# STM32F103C8T6_MinimumCoreBoard.net
KiCad netlist of a schematic drawn in Altium Designer
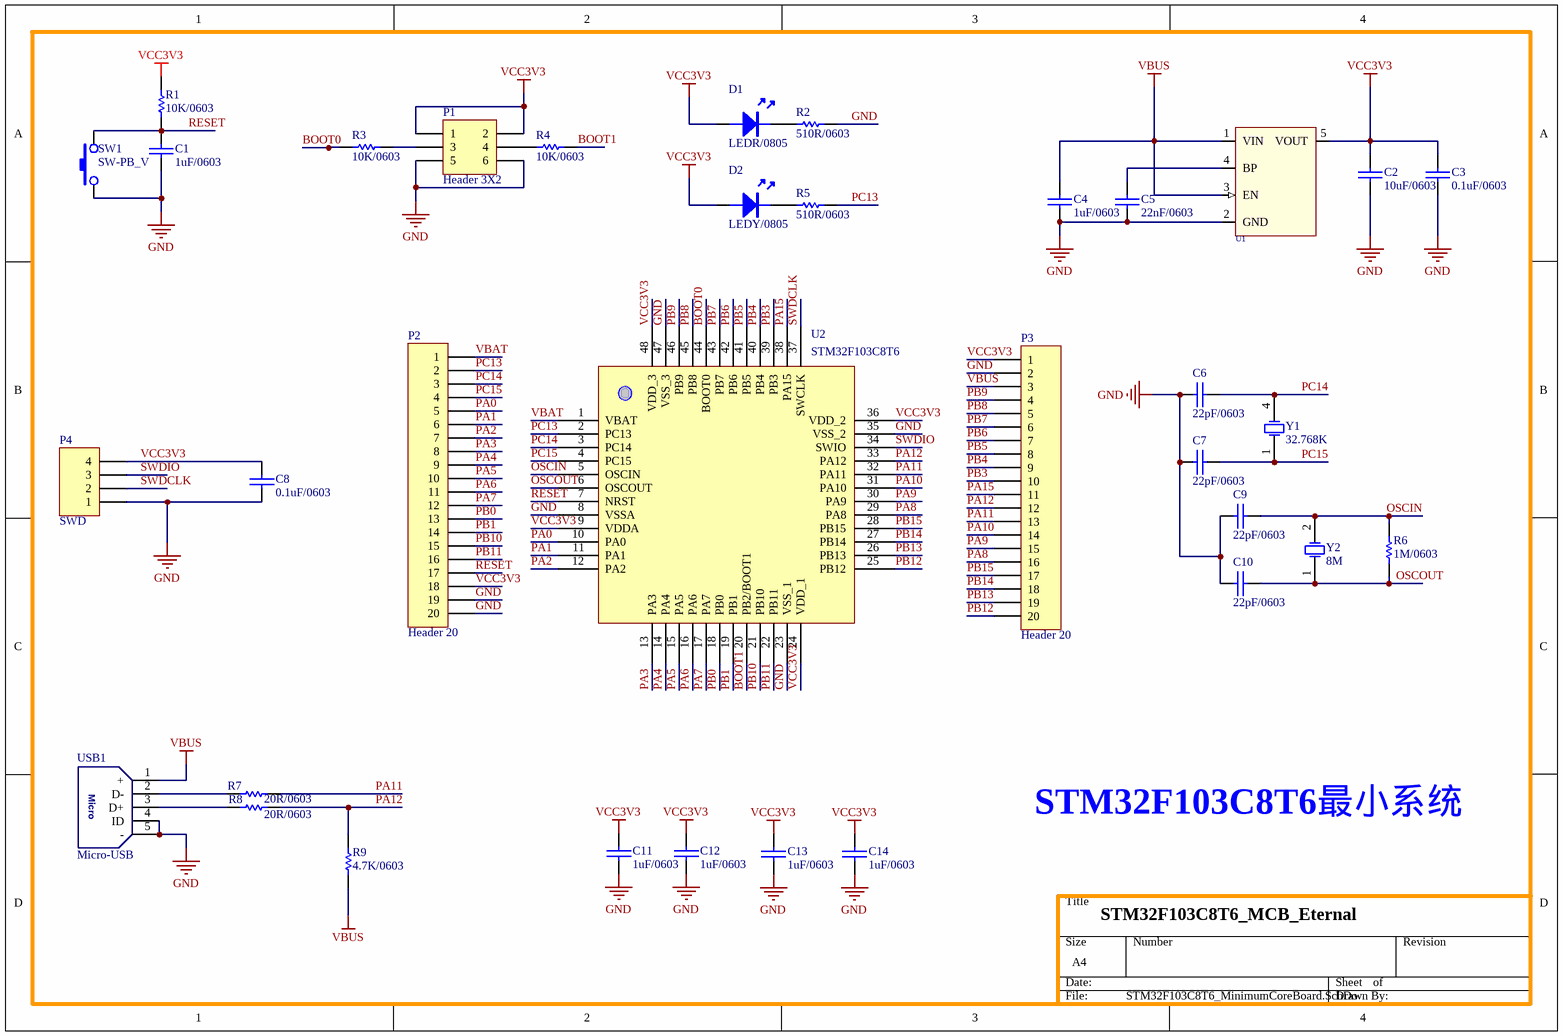
[diagram p0: STM32F103C8T6_MinimumCoreBoard.SchDoc]

(export (version "E")
  (design (tool "Eeschema 10.0.6"))
  (components
    (comp (ref "C1")
      (value "1uF/0603")
      (footprint "0603C")
      (description "无极性电容")
      (libsource (lib "电容") (part "CAP"))
    )
    (comp (ref "C2")
      (value "10uF/0603")
      (footprint "0603C")
      (description "无极性电容")
      (libsource (lib "电容") (part "CAP"))
    )
    (comp (ref "C3")
      (value "0.1uF/0603")
      (footprint "0603C")
      (description "无极性电容")
      (libsource (lib "电容") (part "CAP"))
    )
    (comp (ref "C4")
      (value "1uF/0603")
      (footprint "0603C")
      (description "无极性电容")
      (libsource (lib "电容") (part "CAP"))
    )
    (comp (ref "C5")
      (value "22nF/0603")
      (footprint "0603C")
      (description "无极性电容")
      (libsource (lib "电容") (part "CAP"))
    )
    (comp (ref "C6")
      (value "22pF/0603")
      (footprint "0603C")
      (description "无极性电容")
      (libsource (lib "电容") (part "CAP"))
    )
    (comp (ref "C7")
      (value "22pF/0603")
      (footprint "0603C")
      (description "无极性电容")
      (libsource (lib "电容") (part "CAP"))
    )
    (comp (ref "C8")
      (value "0.1uF/0603")
      (footprint "0603C")
      (description "无极性电容")
      (libsource (lib "电容") (part "CAP"))
    )
    (comp (ref "C9")
      (value "22pF/0603")
      (footprint "0603C")
      (description "无极性电容")
      (libsource (lib "电容") (part "CAP"))
    )
    (comp (ref "C10")
      (value "22pF/0603")
      (footprint "0603C")
      (description "无极性电容")
      (libsource (lib "电容") (part "CAP"))
    )
    (comp (ref "C11")
      (value "1uF/0603")
      (footprint "0603C")
      (description "无极性电容")
      (libsource (lib "电容") (part "CAP"))
    )
    (comp (ref "C12")
      (value "1uF/0603")
      (footprint "0603C")
      (description "无极性电容")
      (libsource (lib "电容") (part "CAP"))
    )
    (comp (ref "C13")
      (value "1uF/0603")
      (footprint "0603C")
      (description "无极性电容")
      (libsource (lib "电容") (part "CAP"))
    )
    (comp (ref "C14")
      (value "1uF/0603")
      (footprint "0603C")
      (description "无极性电容")
      (libsource (lib "电容") (part "CAP"))
    )
    (comp (ref "D1") (value "LEDR/0805") (footprint "LED-0805R") (libsource (lib "LED") (part "LED")))
    (comp (ref "D2") (value "LEDY/0805") (footprint "LED-0805Y") (libsource (lib "LED") (part "LED")))
    (comp (ref "P1")
      (value "Header 3X2")
      (footprint "HDR-3X2")
      (description "Header, 3-Pin, Dual row")
      (fields (field (name "PUBLISHER") "Altium Limited"))
      (libsource (lib "STM32F103C8T6") (part "Header 3X2"))
    )
    (comp (ref "P2")
      (value "Header 20")
      (footprint "HDR1X20")
      (description "Header, 20-Pin")
      (fields (field (name "PUBLISHER") "Altium Limited"))
      (libsource (lib "STM32F103C8T6") (part "Header 20"))
    )
    (comp (ref "P3")
      (value "Header 20")
      (footprint "HDR1X20")
      (description "Header, 20-Pin")
      (fields (field (name "PUBLISHER") "Altium Limited"))
      (libsource (lib "") (part "Header 20_1"))
    )
    (comp (ref "P4")
      (value "SWD")
      (footprint "HDR-1X4_H")
      (description "Header, 4-Pin")
      (fields (field (name "PUBLISHER") "Altium Limited"))
      (libsource (lib "STM32F103C8T6") (part "Header 4"))
    )
    (comp (ref "R1") (value "10K/0603") (footprint "0603R") (libsource (lib "电阻") (part "RES")))
    (comp (ref "R2") (value "510R/0603") (footprint "0603R") (libsource (lib "电阻") (part "RES")))
    (comp (ref "R3") (value "10K/0603") (footprint "0603R") (libsource (lib "电阻") (part "RES")))
    (comp (ref "R4") (value "10K/0603") (footprint "0603R") (libsource (lib "电阻") (part "RES")))
    (comp (ref "R5") (value "510R/0603") (footprint "0603R") (libsource (lib "电阻") (part "RES")))
    (comp (ref "R6") (value "1M/0603") (footprint "0603R") (libsource (lib "电阻") (part "RES")))
    (comp (ref "R7") (value "20R/0603") (footprint "0603R") (libsource (lib "电阻") (part "RES")))
    (comp (ref "R8") (value "20R/0603") (footprint "0603R") (libsource (lib "电阻") (part "RES")))
    (comp (ref "R9") (value "4.7K/0603") (footprint "0603R") (libsource (lib "电阻") (part "RES")))
    (comp (ref "SW1")
      (value "SW-PB_V")
      (footprint "TSW SMD-3*6*2.5")
      (description "SWITCH")
      (libsource (lib "STM32F103C8T6") (part "SW-PB_V"))
    )
    (comp (ref "U1")
      (value "RT9193")
      (footprint "SOT23-5L")
      (fields (field (name "ICA_PARTNUM") "$$2191094$$RT9193-15CU5") (field (name "PART NUMBER") "TMP-13"))
      (libsource (lib "STM32F103C8T6") (part "RT9193X_5P"))
    )
    (comp (ref "U2")
      (value "STM32F103C8T6")
      (footprint "TQFP48 7x7_L")
      (libsource (lib "STM32F103C8T6") (part "STM32F103C8T6"))
    )
    (comp (ref "USB1")
      (value "Micro-USB")
      (footprint "USB-micro_B")
      (libsource (lib "USB") (part "Micro-USB"))
    )
    (comp (ref "Y1")
      (value "32.768K")
      (footprint "MC-306")
      (description "Crystal Oscillator")
      (fields (field (name "PUBLISHER") "Altium Limited"))
      (libsource (lib "") (part "XTAL_1"))
    )
    (comp (ref "Y2")
      (value "8M")
      (footprint "XTAL-49S DIP")
      (description "Crystal Oscillator")
      (fields (field (name "PUBLISHER") "Altium Limited"))
      (libsource (lib "STM32F103C8T6") (part "XTAL"))
    )
  )
  (nets
    (net (code "1") (name "/BOOT0") (class "Default")
      (node (ref "R3") (pin "1") (pinfunction "1_1") (pintype "passive"))
      (node (ref "U2") (pin "44") (pinfunction "BOOT0_44") (pintype "passive"))
    )
    (net (code "2") (name "/BOOT1") (class "Default")
      (node (ref "R4") (pin "2") (pinfunction "2_2") (pintype "passive"))
      (node (ref "U2") (pin "20") (pinfunction "PB2/BOOT1_20") (pintype "passive"))
    )
    (net (code "3") (name "/OSCIN") (class "Default")
      (node (ref "C9") (pin "1") (pinfunction "1_1") (pintype "passive"))
      (node (ref "R6") (pin "2") (pinfunction "2_2") (pintype "passive"))
      (node (ref "U2") (pin "5") (pinfunction "OSCIN_5") (pintype "passive"))
      (node (ref "Y2") (pin "2") (pinfunction "OSC2_2") (pintype "passive"))
    )
    (net (code "4") (name "/OSCOUT") (class "Default")
      (node (ref "C10") (pin "1") (pinfunction "1_1") (pintype "passive"))
      (node (ref "R6") (pin "1") (pinfunction "1_1") (pintype "passive"))
      (node (ref "U2") (pin "6") (pinfunction "OSCOUT_6") (pintype "passive"))
      (node (ref "Y2") (pin "1") (pinfunction "OSC1_1") (pintype "passive"))
    )
    (net (code "5") (name "/PA0") (class "Default")
      (node (ref "P2") (pin "5") (pinfunction "5_5") (pintype "passive"))
      (node (ref "U2") (pin "10") (pinfunction "PA0_10") (pintype "passive"))
    )
    (net (code "6") (name "/PA1") (class "Default")
      (node (ref "P2") (pin "6") (pinfunction "6_6") (pintype "passive"))
      (node (ref "U2") (pin "11") (pinfunction "PA1_11") (pintype "passive"))
    )
    (net (code "7") (name "/PA2") (class "Default")
      (node (ref "P2") (pin "7") (pinfunction "7_7") (pintype "passive"))
      (node (ref "U2") (pin "12") (pinfunction "PA2_12") (pintype "passive"))
    )
    (net (code "8") (name "/PA3") (class "Default")
      (node (ref "P2") (pin "8") (pinfunction "8_8") (pintype "passive"))
      (node (ref "U2") (pin "13") (pinfunction "PA3_13") (pintype "passive"))
    )
    (net (code "9") (name "/PA4") (class "Default")
      (node (ref "P2") (pin "9") (pinfunction "9_9") (pintype "passive"))
      (node (ref "U2") (pin "14") (pinfunction "PA4_14") (pintype "passive"))
    )
    (net (code "10") (name "/PA5") (class "Default")
      (node (ref "P2") (pin "10") (pinfunction "10_10") (pintype "passive"))
      (node (ref "U2") (pin "15") (pinfunction "PA5_15") (pintype "passive"))
    )
    (net (code "11") (name "/PA6") (class "Default")
      (node (ref "P2") (pin "11") (pinfunction "11_11") (pintype "passive"))
      (node (ref "U2") (pin "16") (pinfunction "PA6_16") (pintype "passive"))
    )
    (net (code "12") (name "/PA7") (class "Default")
      (node (ref "P2") (pin "12") (pinfunction "12_12") (pintype "passive"))
      (node (ref "U2") (pin "17") (pinfunction "PA7_17") (pintype "passive"))
    )
    (net (code "13") (name "/PA8") (class "Default")
      (node (ref "P3") (pin "16") (pinfunction "16_16") (pintype "passive"))
      (node (ref "U2") (pin "29") (pinfunction "PA8_29") (pintype "passive"))
    )
    (net (code "14") (name "/PA9") (class "Default")
      (node (ref "P3") (pin "15") (pinfunction "15_15") (pintype "passive"))
      (node (ref "U2") (pin "30") (pinfunction "PA9_30") (pintype "passive"))
    )
    (net (code "15") (name "/PA10") (class "Default")
      (node (ref "P3") (pin "14") (pinfunction "14_14") (pintype "passive"))
      (node (ref "U2") (pin "31") (pinfunction "PA10_31") (pintype "passive"))
    )
    (net (code "16") (name "/PA11") (class "Default")
      (node (ref "P3") (pin "13") (pinfunction "13_13") (pintype "passive"))
      (node (ref "R7") (pin "2") (pinfunction "2_2") (pintype "passive"))
      (node (ref "U2") (pin "32") (pinfunction "PA11_32") (pintype "passive"))
    )
    (net (code "17") (name "/PA12") (class "Default")
      (node (ref "P3") (pin "12") (pinfunction "12_12") (pintype "passive"))
      (node (ref "R8") (pin "2") (pinfunction "2_2") (pintype "passive"))
      (node (ref "R9") (pin "2") (pinfunction "2_2") (pintype "passive"))
      (node (ref "U2") (pin "33") (pinfunction "PA12_33") (pintype "passive"))
    )
    (net (code "18") (name "/PA15") (class "Default")
      (node (ref "P3") (pin "11") (pinfunction "11_11") (pintype "passive"))
      (node (ref "U2") (pin "38") (pinfunction "PA15_38") (pintype "passive"))
    )
    (net (code "19") (name "/PB0") (class "Default")
      (node (ref "P2") (pin "13") (pinfunction "13_13") (pintype "passive"))
      (node (ref "U2") (pin "18") (pinfunction "PB0_18") (pintype "passive"))
    )
    (net (code "20") (name "/PB1") (class "Default")
      (node (ref "P2") (pin "14") (pinfunction "14_14") (pintype "passive"))
      (node (ref "U2") (pin "19") (pinfunction "PB1_19") (pintype "passive"))
    )
    (net (code "21") (name "/PB3") (class "Default")
      (node (ref "P3") (pin "10") (pinfunction "10_10") (pintype "passive"))
      (node (ref "U2") (pin "39") (pinfunction "PB3_39") (pintype "passive"))
    )
    (net (code "22") (name "/PB4") (class "Default")
      (node (ref "P3") (pin "9") (pinfunction "9_9") (pintype "passive"))
      (node (ref "U2") (pin "40") (pinfunction "PB4_40") (pintype "passive"))
    )
    (net (code "23") (name "/PB5") (class "Default")
      (node (ref "P3") (pin "8") (pinfunction "8_8") (pintype "passive"))
      (node (ref "U2") (pin "41") (pinfunction "PB5_41") (pintype "passive"))
    )
    (net (code "24") (name "/PB6") (class "Default")
      (node (ref "P3") (pin "7") (pinfunction "7_7") (pintype "passive"))
      (node (ref "U2") (pin "42") (pinfunction "PB6_42") (pintype "passive"))
    )
    (net (code "25") (name "/PB7") (class "Default")
      (node (ref "P3") (pin "6") (pinfunction "6_6") (pintype "passive"))
      (node (ref "U2") (pin "43") (pinfunction "PB7_43") (pintype "passive"))
    )
    (net (code "26") (name "/PB8") (class "Default")
      (node (ref "P3") (pin "5") (pinfunction "5_5") (pintype "passive"))
      (node (ref "U2") (pin "45") (pinfunction "PB8_45") (pintype "passive"))
    )
    (net (code "27") (name "/PB9") (class "Default")
      (node (ref "P3") (pin "4") (pinfunction "4_4") (pintype "passive"))
      (node (ref "U2") (pin "46") (pinfunction "PB9_46") (pintype "passive"))
    )
    (net (code "28") (name "/PB10") (class "Default")
      (node (ref "P2") (pin "15") (pinfunction "15_15") (pintype "passive"))
      (node (ref "U2") (pin "21") (pinfunction "PB10_21") (pintype "passive"))
    )
    (net (code "29") (name "/PB11") (class "Default")
      (node (ref "P2") (pin "16") (pinfunction "16_16") (pintype "passive"))
      (node (ref "U2") (pin "22") (pinfunction "PB11_22") (pintype "passive"))
    )
    (net (code "30") (name "/PB12") (class "Default")
      (node (ref "P3") (pin "20") (pinfunction "20_20") (pintype "passive"))
      (node (ref "U2") (pin "25") (pinfunction "PB12_25") (pintype "passive"))
    )
    (net (code "31") (name "/PB13") (class "Default")
      (node (ref "P3") (pin "19") (pinfunction "19_19") (pintype "passive"))
      (node (ref "U2") (pin "26") (pinfunction "PB13_26") (pintype "passive"))
    )
    (net (code "32") (name "/PB14") (class "Default")
      (node (ref "P3") (pin "18") (pinfunction "18_18") (pintype "passive"))
      (node (ref "U2") (pin "27") (pinfunction "PB14_27") (pintype "passive"))
    )
    (net (code "33") (name "/PB15") (class "Default")
      (node (ref "P3") (pin "17") (pinfunction "17_17") (pintype "passive"))
      (node (ref "U2") (pin "28") (pinfunction "PB15_28") (pintype "passive"))
    )
    (net (code "34") (name "/PC13") (class "Default")
      (node (ref "P2") (pin "2") (pinfunction "2_2") (pintype "passive"))
      (node (ref "R5") (pin "2") (pinfunction "2_2") (pintype "passive"))
      (node (ref "U2") (pin "2") (pinfunction "PC13_2") (pintype "passive"))
    )
    (net (code "35") (name "/PC14") (class "Default")
      (node (ref "C6") (pin "1") (pinfunction "1_1") (pintype "passive"))
      (node (ref "P2") (pin "3") (pinfunction "3_3") (pintype "passive"))
      (node (ref "U2") (pin "3") (pinfunction "PC14_3") (pintype "passive"))
      (node (ref "Y1") (pin "4") (pinfunction "OSC2_4") (pintype "passive"))
    )
    (net (code "36") (name "/PC15") (class "Default")
      (node (ref "C7") (pin "1") (pinfunction "1_1") (pintype "passive"))
      (node (ref "P2") (pin "4") (pinfunction "4_4") (pintype "passive"))
      (node (ref "U2") (pin "4") (pinfunction "PC15_4") (pintype "passive"))
      (node (ref "Y1") (pin "1") (pinfunction "OSC1_1") (pintype "passive"))
    )
    (net (code "37") (name "/RESET") (class "Default")
      (node (ref "C1") (pin "2") (pinfunction "2_2") (pintype "passive"))
      (node (ref "P2") (pin "17") (pinfunction "17_17") (pintype "passive"))
      (node (ref "R1") (pin "2") (pinfunction "2_2") (pintype "passive"))
      (node (ref "SW1") (pin "2") (pinfunction "2_2") (pintype "passive"))
      (node (ref "U2") (pin "7") (pinfunction "NRST_7") (pintype "passive"))
    )
    (net (code "38") (name "/SWDCLK") (class "Default")
      (node (ref "P4") (pin "2") (pinfunction "2_2") (pintype "passive"))
      (node (ref "U2") (pin "37") (pinfunction "SWCLK_37") (pintype "passive"))
    )
    (net (code "39") (name "/SWDIO") (class "Default")
      (node (ref "P4") (pin "3") (pinfunction "3_3") (pintype "passive"))
      (node (ref "U2") (pin "34") (pinfunction "SWIO_34") (pintype "passive"))
    )
    (net (code "40") (name "/VBAT") (class "Default")
      (node (ref "P2") (pin "1") (pinfunction "1_1") (pintype "passive"))
      (node (ref "U2") (pin "1") (pinfunction "VBAT_1") (pintype "passive"))
    )
    (net (code "41") (name "GND") (class "Default")
      (node (ref "C1") (pin "1") (pinfunction "1_1") (pintype "passive"))
      (node (ref "C10") (pin "2") (pinfunction "2_2") (pintype "passive"))
      (node (ref "C11") (pin "1") (pinfunction "1_1") (pintype "passive"))
      (node (ref "C12") (pin "1") (pinfunction "1_1") (pintype "passive"))
      (node (ref "C13") (pin "1") (pinfunction "1_1") (pintype "passive"))
      (node (ref "C14") (pin "1") (pinfunction "1_1") (pintype "passive"))
      (node (ref "C2") (pin "1") (pinfunction "1_1") (pintype "passive"))
      (node (ref "C3") (pin "1") (pinfunction "1_1") (pintype "passive"))
      (node (ref "C4") (pin "1") (pinfunction "1_1") (pintype "passive"))
      (node (ref "C5") (pin "1") (pinfunction "1_1") (pintype "passive"))
      (node (ref "C6") (pin "2") (pinfunction "2_2") (pintype "passive"))
      (node (ref "C7") (pin "2") (pinfunction "2_2") (pintype "passive"))
      (node (ref "C8") (pin "1") (pinfunction "1_1") (pintype "passive"))
      (node (ref "C9") (pin "2") (pinfunction "2_2") (pintype "passive"))
      (node (ref "P1") (pin "5") (pinfunction "5_5") (pintype "passive"))
      (node (ref "P1") (pin "6") (pinfunction "6_6") (pintype "passive"))
      (node (ref "P2") (pin "19") (pinfunction "19_19") (pintype "passive"))
      (node (ref "P2") (pin "20") (pinfunction "20_20") (pintype "passive"))
      (node (ref "P3") (pin "2") (pinfunction "2_2") (pintype "passive"))
      (node (ref "P4") (pin "1") (pinfunction "1_1") (pintype "passive"))
      (node (ref "R2") (pin "2") (pinfunction "2_2") (pintype "passive"))
      (node (ref "SW1") (pin "1") (pinfunction "1_1") (pintype "passive"))
      (node (ref "U1") (pin "2") (pinfunction "GND_2") (pintype "power_in"))
      (node (ref "U2") (pin "23") (pinfunction "VSS_1_23") (pintype "passive"))
      (node (ref "U2") (pin "35") (pinfunction "VSS_2_35") (pintype "passive"))
      (node (ref "U2") (pin "47") (pinfunction "VSS_3_47") (pintype "passive"))
      (node (ref "U2") (pin "8") (pinfunction "VSSA_8") (pintype "passive"))
      (node (ref "USB1") (pin "4") (pinfunction "ID_4") (pintype "passive"))
      (node (ref "USB1") (pin "5") (pinfunction "-_5") (pintype "passive"))
    )
    (net (code "42") (name "Net-(D1-PadK)") (class "Default")
      (node (ref "D1") (pin "K") (pinfunction "K_K") (pintype "passive"))
      (node (ref "R2") (pin "1") (pinfunction "1_1") (pintype "passive"))
    )
    (net (code "43") (name "Net-(D2-PadK)") (class "Default")
      (node (ref "D2") (pin "K") (pinfunction "K_K") (pintype "passive"))
      (node (ref "R5") (pin "1") (pinfunction "1_1") (pintype "passive"))
    )
    (net (code "44") (name "Net-(P1-Pad3)") (class "Default")
      (node (ref "P1") (pin "3") (pinfunction "3_3") (pintype "passive"))
      (node (ref "R3") (pin "2") (pinfunction "2_2") (pintype "passive"))
    )
    (net (code "45") (name "Net-(P1-Pad4)") (class "Default")
      (node (ref "P1") (pin "4") (pinfunction "4_4") (pintype "passive"))
      (node (ref "R4") (pin "1") (pinfunction "1_1") (pintype "passive"))
    )
    (net (code "46") (name "Net-(U1-BP)") (class "Default")
      (node (ref "C5") (pin "2") (pinfunction "2_2") (pintype "passive"))
      (node (ref "U1") (pin "4") (pinfunction "BP_4") (pintype "passive"))
    )
    (net (code "47") (name "Net-(USB1-D+)") (class "Default")
      (node (ref "R8") (pin "1") (pinfunction "1_1") (pintype "passive"))
      (node (ref "USB1") (pin "3") (pinfunction "D+_3") (pintype "passive"))
    )
    (net (code "48") (name "Net-(USB1-D-)") (class "Default")
      (node (ref "R7") (pin "1") (pinfunction "1_1") (pintype "passive"))
      (node (ref "USB1") (pin "2") (pinfunction "D-_2") (pintype "passive"))
    )
    (net (code "49") (name "VBUS") (class "Default")
      (node (ref "C4") (pin "2") (pinfunction "2_2") (pintype "passive"))
      (node (ref "P3") (pin "3") (pinfunction "3_3") (pintype "passive"))
      (node (ref "R9") (pin "1") (pinfunction "1_1") (pintype "passive"))
      (node (ref "U1") (pin "1") (pinfunction "VIN_1") (pintype "power_in"))
      (node (ref "U1") (pin "3") (pinfunction "EN_3") (pintype "input"))
      (node (ref "USB1") (pin "1") (pinfunction "+_1") (pintype "passive"))
    )
    (net (code "50") (name "VCC3V3") (class "Default")
      (node (ref "C11") (pin "2") (pinfunction "2_2") (pintype "passive"))
      (node (ref "C12") (pin "2") (pinfunction "2_2") (pintype "passive"))
      (node (ref "C13") (pin "2") (pinfunction "2_2") (pintype "passive"))
      (node (ref "C14") (pin "2") (pinfunction "2_2") (pintype "passive"))
      (node (ref "C2") (pin "2") (pinfunction "2_2") (pintype "passive"))
      (node (ref "C3") (pin "2") (pinfunction "2_2") (pintype "passive"))
      (node (ref "C8") (pin "2") (pinfunction "2_2") (pintype "passive"))
      (node (ref "D1") (pin "A") (pinfunction "A_A") (pintype "passive"))
      (node (ref "D2") (pin "A") (pinfunction "A_A") (pintype "passive"))
      (node (ref "P1") (pin "1") (pinfunction "1_1") (pintype "passive"))
      (node (ref "P1") (pin "2") (pinfunction "2_2") (pintype "passive"))
      (node (ref "P2") (pin "18") (pinfunction "18_18") (pintype "passive"))
      (node (ref "P3") (pin "1") (pinfunction "1_1") (pintype "passive"))
      (node (ref "P4") (pin "4") (pinfunction "4_4") (pintype "passive"))
      (node (ref "R1") (pin "1") (pinfunction "1_1") (pintype "passive"))
      (node (ref "U1") (pin "5") (pinfunction "VOUT_5") (pintype "power_in"))
      (node (ref "U2") (pin "24") (pinfunction "VDD_1_24") (pintype "passive"))
      (node (ref "U2") (pin "36") (pinfunction "VDD_2_36") (pintype "passive"))
      (node (ref "U2") (pin "48") (pinfunction "VDD_3_48") (pintype "passive"))
      (node (ref "U2") (pin "9") (pinfunction "VDDA_9") (pintype "passive"))
    )
  )
)
